# PLT-01-RevA.net
KiCad netlist of a schematic drawn in EAGLE
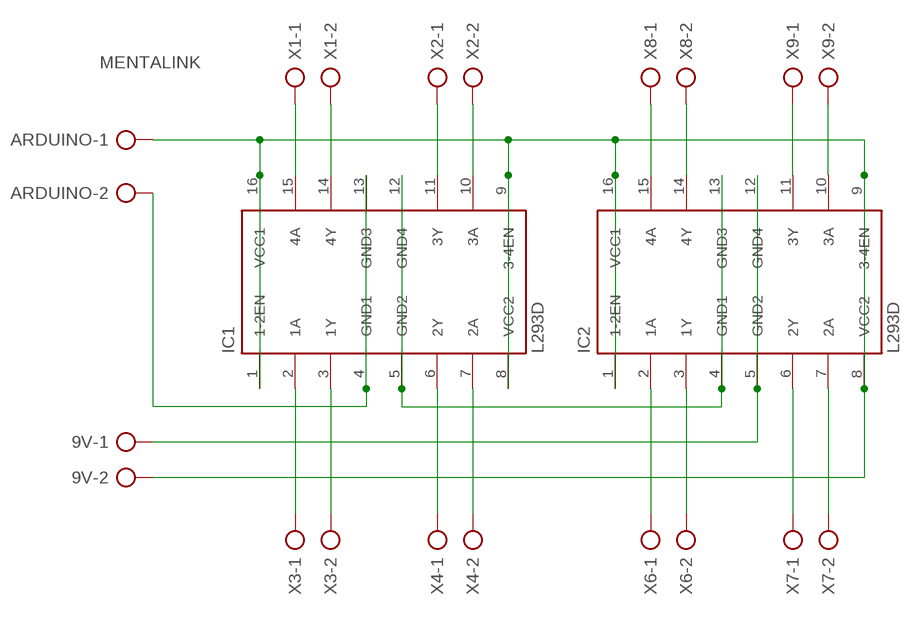
[diagram p0: schematic, sheet 1]

(export (version "E")
  (design (tool "Eeschema 10.0.6"))
  (components
    (comp (ref "9V")
      (value "AK300/2")
      (footprint "eagle-import:AK300_2")
      (libsource (lib "eagle-import") (part "AK300/2"))
    )
    (comp (ref "ARDUINO")
      (value "AK300/2")
      (footprint "eagle-import:AK300_2")
      (libsource (lib "eagle-import") (part "AK300/2"))
    )
    (comp (ref "IC1")
      (value "L293D")
      (footprint "eagle-import:DIL16")
      (libsource (lib "eagle-import") (part "L293D"))
    )
    (comp (ref "IC2")
      (value "L293D")
      (footprint "eagle-import:DIL16")
      (libsource (lib "eagle-import") (part "L293D"))
    )
    (comp (ref "X1")
      (value "AK300/2")
      (footprint "eagle-import:AK300_2")
      (libsource (lib "eagle-import") (part "AK300/2"))
    )
    (comp (ref "X2")
      (value "AK300/2")
      (footprint "eagle-import:AK300_2")
      (libsource (lib "eagle-import") (part "AK300/2"))
    )
    (comp (ref "X3")
      (value "AK300/2")
      (footprint "eagle-import:AK300_2")
      (libsource (lib "eagle-import") (part "AK300/2"))
    )
    (comp (ref "X4")
      (value "AK300/2")
      (footprint "eagle-import:AK300_2")
      (libsource (lib "eagle-import") (part "AK300/2"))
    )
    (comp (ref "X6")
      (value "AK300/2")
      (footprint "eagle-import:AK300_2")
      (libsource (lib "eagle-import") (part "AK300/2"))
    )
    (comp (ref "X7")
      (value "AK300/2")
      (footprint "eagle-import:AK300_2")
      (libsource (lib "eagle-import") (part "AK300/2"))
    )
    (comp (ref "X8")
      (value "AK300/2")
      (footprint "eagle-import:AK300_2")
      (libsource (lib "eagle-import") (part "AK300/2"))
    )
    (comp (ref "X9")
      (value "AK300/2")
      (footprint "eagle-import:AK300_2")
      (libsource (lib "eagle-import") (part "AK300/2"))
    )
  )
  (nets
    (net (code "1") (name "Net-(9VA-KL)") (class "Default")
      (node (ref "9V") (pin "1") (pinfunction "KL_1") (pintype "passive"))
      (node (ref "IC2") (pin "12") (pinfunction "GND4_12") (pintype "power_in"))
      (node (ref "IC2") (pin "5") (pinfunction "GND2_5") (pintype "power_in"))
    )
    (net (code "2") (name "Net-(9VB-KL)") (class "Default")
      (node (ref "9V") (pin "2") (pinfunction "KL_2") (pintype "passive"))
      (node (ref "ARDUINO") (pin "1") (pinfunction "KL_1") (pintype "passive"))
      (node (ref "IC1") (pin "1") (pinfunction "1-2EN_1") (pintype "input"))
      (node (ref "IC1") (pin "16") (pinfunction "VCC1_16") (pintype "power_in"))
      (node (ref "IC1") (pin "8") (pinfunction "VCC2_8") (pintype "power_in"))
      (node (ref "IC1") (pin "9") (pinfunction "3-4EN_9") (pintype "input"))
      (node (ref "IC2") (pin "1") (pinfunction "1-2EN_1") (pintype "input"))
      (node (ref "IC2") (pin "16") (pinfunction "VCC1_16") (pintype "power_in"))
      (node (ref "IC2") (pin "8") (pinfunction "VCC2_8") (pintype "power_in"))
      (node (ref "IC2") (pin "9") (pinfunction "3-4EN_9") (pintype "input"))
    )
    (net (code "3") (name "Net-(ARDUINOB-KL)") (class "Default")
      (node (ref "ARDUINO") (pin "2") (pinfunction "KL_2") (pintype "passive"))
      (node (ref "IC1") (pin "13") (pinfunction "GND3_13") (pintype "power_in"))
      (node (ref "IC1") (pin "4") (pinfunction "GND1_4") (pintype "power_in"))
    )
    (net (code "4") (name "Net-(IC1-1A)") (class "Default")
      (node (ref "IC1") (pin "2") (pinfunction "1A_2") (pintype "input"))
      (node (ref "X3") (pin "1") (pinfunction "KL_1") (pintype "passive"))
    )
    (net (code "5") (name "Net-(IC1-1Y)") (class "Default")
      (node (ref "IC1") (pin "3") (pinfunction "1Y_3") (pintype "output"))
      (node (ref "X3") (pin "2") (pinfunction "KL_2") (pintype "passive"))
    )
    (net (code "6") (name "Net-(IC1-2A)") (class "Default")
      (node (ref "IC1") (pin "7") (pinfunction "2A_7") (pintype "input"))
      (node (ref "X4") (pin "2") (pinfunction "KL_2") (pintype "passive"))
    )
    (net (code "7") (name "Net-(IC1-2Y)") (class "Default")
      (node (ref "IC1") (pin "6") (pinfunction "2Y_6") (pintype "output"))
      (node (ref "X4") (pin "1") (pinfunction "KL_1") (pintype "passive"))
    )
    (net (code "8") (name "Net-(IC1-3A)") (class "Default")
      (node (ref "IC1") (pin "10") (pinfunction "3A_10") (pintype "input"))
      (node (ref "X2") (pin "2") (pinfunction "KL_2") (pintype "passive"))
    )
    (net (code "9") (name "Net-(IC1-3Y)") (class "Default")
      (node (ref "IC1") (pin "11") (pinfunction "3Y_11") (pintype "output"))
      (node (ref "X2") (pin "1") (pinfunction "KL_1") (pintype "passive"))
    )
    (net (code "10") (name "Net-(IC1-4A)") (class "Default")
      (node (ref "IC1") (pin "15") (pinfunction "4A_15") (pintype "input"))
      (node (ref "X1") (pin "1") (pinfunction "KL_1") (pintype "passive"))
    )
    (net (code "11") (name "Net-(IC1-4Y)") (class "Default")
      (node (ref "IC1") (pin "14") (pinfunction "4Y_14") (pintype "output"))
      (node (ref "X1") (pin "2") (pinfunction "KL_2") (pintype "passive"))
    )
    (net (code "12") (name "Net-(IC1-GND2)") (class "Default")
      (node (ref "IC1") (pin "12") (pinfunction "GND4_12") (pintype "power_in"))
      (node (ref "IC1") (pin "5") (pinfunction "GND2_5") (pintype "power_in"))
      (node (ref "IC2") (pin "13") (pinfunction "GND3_13") (pintype "power_in"))
      (node (ref "IC2") (pin "4") (pinfunction "GND1_4") (pintype "power_in"))
    )
    (net (code "13") (name "Net-(IC2-1A)") (class "Default")
      (node (ref "IC2") (pin "2") (pinfunction "1A_2") (pintype "input"))
      (node (ref "X6") (pin "1") (pinfunction "KL_1") (pintype "passive"))
    )
    (net (code "14") (name "Net-(IC2-1Y)") (class "Default")
      (node (ref "IC2") (pin "3") (pinfunction "1Y_3") (pintype "output"))
      (node (ref "X6") (pin "2") (pinfunction "KL_2") (pintype "passive"))
    )
    (net (code "15") (name "Net-(IC2-2A)") (class "Default")
      (node (ref "IC2") (pin "7") (pinfunction "2A_7") (pintype "input"))
      (node (ref "X7") (pin "2") (pinfunction "KL_2") (pintype "passive"))
    )
    (net (code "16") (name "Net-(IC2-2Y)") (class "Default")
      (node (ref "IC2") (pin "6") (pinfunction "2Y_6") (pintype "output"))
      (node (ref "X7") (pin "1") (pinfunction "KL_1") (pintype "passive"))
    )
    (net (code "17") (name "Net-(IC2-3A)") (class "Default")
      (node (ref "IC2") (pin "10") (pinfunction "3A_10") (pintype "input"))
      (node (ref "X9") (pin "2") (pinfunction "KL_2") (pintype "passive"))
    )
    (net (code "18") (name "Net-(IC2-3Y)") (class "Default")
      (node (ref "IC2") (pin "11") (pinfunction "3Y_11") (pintype "output"))
      (node (ref "X9") (pin "1") (pinfunction "KL_1") (pintype "passive"))
    )
    (net (code "19") (name "Net-(IC2-4A)") (class "Default")
      (node (ref "IC2") (pin "15") (pinfunction "4A_15") (pintype "input"))
      (node (ref "X8") (pin "1") (pinfunction "KL_1") (pintype "passive"))
    )
    (net (code "20") (name "Net-(IC2-4Y)") (class "Default")
      (node (ref "IC2") (pin "14") (pinfunction "4Y_14") (pintype "output"))
      (node (ref "X8") (pin "2") (pinfunction "KL_2") (pintype "passive"))
    )
  )
)
